# esp8266_ver3.net
KiCad netlist of a schematic drawn in EAGLE
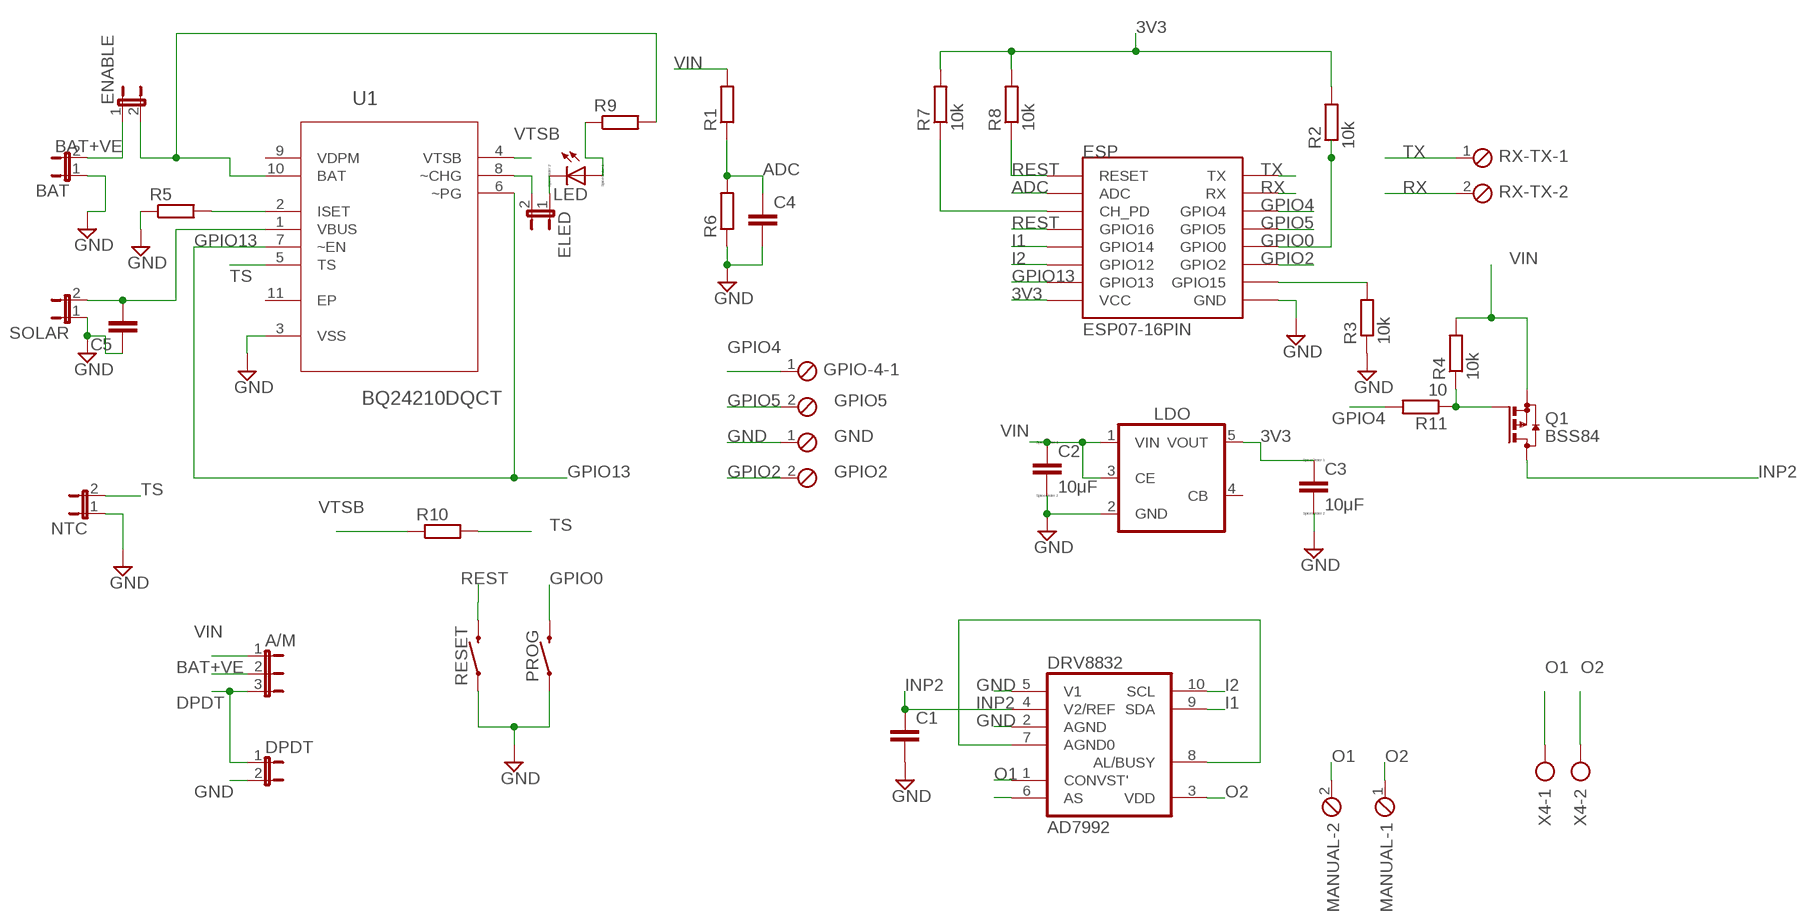
[diagram p0: schematic, sheet 1]

(export (version "E")
  (design (tool "Eeschema 10.0.6"))
  (components
    (comp (ref "A/M")
      (value "JP2E")
      (footprint "eagle-import:JP2")
      (libsource (lib "eagle-import") (part "JP2E"))
    )
    (comp (ref "BAT")
      (value "JP1E")
      (footprint "eagle-import:JP1")
      (libsource (lib "eagle-import") (part "JP1E"))
    )
    (comp (ref "C1")
      (value "C-EUC0805K")
      (footprint "eagle-import:C0805K")
      (libsource (lib "eagle-import") (part "C-EUC0805K"))
    )
    (comp (ref "C2")
      (value "10μF")
      (footprint "eagle-import:C1206")
      (libsource (lib "eagle-import") (part "CC1206"))
    )
    (comp (ref "C3")
      (value "10μF")
      (footprint "eagle-import:C1206")
      (libsource (lib "eagle-import") (part "CC1206"))
    )
    (comp (ref "C4")
      (value "C-EUC1206")
      (footprint "eagle-import:C1206")
      (libsource (lib "eagle-import") (part "C-EUC1206"))
    )
    (comp (ref "C5")
      (value "C-EUC1206")
      (footprint "eagle-import:C1206")
      (libsource (lib "eagle-import") (part "C-EUC1206"))
    )
    (comp (ref "DPDT")
      (value "JP1E")
      (footprint "eagle-import:JP1")
      (libsource (lib "eagle-import") (part "JP1E"))
    )
    (comp (ref "DRV8832")
      (value "AD7992")
      (footprint "eagle-import:MSOP10")
      (libsource (lib "eagle-import") (part "AD7992"))
    )
    (comp (ref "ELED")
      (value "JP1E")
      (footprint "eagle-import:JP1")
      (libsource (lib "eagle-import") (part "JP1E"))
    )
    (comp (ref "ENABLE")
      (value "JP1E")
      (footprint "eagle-import:JP1")
      (libsource (lib "eagle-import") (part "JP1E"))
    )
    (comp (ref "ESP")
      (value "ESP07-16PIN")
      (footprint "eagle-import:ESP07-16PIN")
      (libsource (lib "eagle-import") (part "ESP07-16PIN"))
    )
    (comp (ref "GPIO-4")
      (value "MPT2")
      (footprint "eagle-import:2POL254")
      (libsource (lib "eagle-import") (part "con-phoenix-254_172_MPT2"))
    )
    (comp (ref "LDO")
      (value "TS5205")
      (footprint "eagle-import:SOT25")
      (libsource (lib "eagle-import") (part "TS5205"))
    )
    (comp (ref "LED")
      (value "LED_E")
      (footprint "eagle-import:LED_1206")
      (libsource (lib "eagle-import") (part "LED_E"))
    )
    (comp (ref "MANUAL")
      (value "MPT2")
      (footprint "eagle-import:2POL254")
      (libsource (lib "eagle-import") (part "con-phoenix-254_172_MPT2"))
    )
    (comp (ref "NTC")
      (value "JP1E")
      (footprint "eagle-import:JP1")
      (libsource (lib "eagle-import") (part "JP1E"))
    )
    (comp (ref "PROG")
      (value "MOMENTARY-SWITCH-SPST-SMD-5.2MM")
      (footprint "eagle-import:TACTILE_SWITCH_SMD_5.2MM")
      (libsource (lib "eagle-import") (part "MOMENTARY-SWITCH-SPST-SMD-5.2MM"))
    )
    (comp (ref "Q1")
      (value "BSS84")
      (footprint "eagle-import:SOT23")
      (libsource (lib "eagle-import") (part "BSS84"))
    )
    (comp (ref "R1")
      (value "R-EU_R1206")
      (footprint "eagle-import:R1206")
      (libsource (lib "eagle-import") (part "resistor_348_R-EU_R1206"))
    )
    (comp (ref "R2")
      (value "10k")
      (footprint "eagle-import:R1206")
      (libsource (lib "eagle-import") (part "R-EU_R1206"))
    )
    (comp (ref "R3")
      (value "10k")
      (footprint "eagle-import:R1206")
      (libsource (lib "eagle-import") (part "R-EU_R1206"))
    )
    (comp (ref "R4")
      (value "10k")
      (footprint "eagle-import:R1206")
      (libsource (lib "eagle-import") (part "resistor_348_R-EU_R1206"))
    )
    (comp (ref "R5")
      (value "R-EU_R1206")
      (footprint "eagle-import:R1206")
      (libsource (lib "eagle-import") (part "resistor_348_R-EU_R1206"))
    )
    (comp (ref "R6")
      (value "R-EU_R1206")
      (footprint "eagle-import:R1206")
      (libsource (lib "eagle-import") (part "resistor_348_R-EU_R1206"))
    )
    (comp (ref "R7")
      (value "10k")
      (footprint "eagle-import:R1206")
      (libsource (lib "eagle-import") (part "R-EU_R1206"))
    )
    (comp (ref "R8")
      (value "10k")
      (footprint "eagle-import:R1206")
      (libsource (lib "eagle-import") (part "R-EU_R1206"))
    )
    (comp (ref "R9")
      (value "R-EU_R1206")
      (footprint "eagle-import:R1206")
      (libsource (lib "eagle-import") (part "resistor_348_R-EU_R1206"))
    )
    (comp (ref "R10")
      (value "R-EU_R1206")
      (footprint "eagle-import:R1206")
      (libsource (lib "eagle-import") (part "resistor_348_R-EU_R1206"))
    )
    (comp (ref "R11")
      (value "10")
      (footprint "eagle-import:R1206")
      (libsource (lib "eagle-import") (part "resistor_348_R-EU_R1206"))
    )
    (comp (ref "RESET")
      (value "MOMENTARY-SWITCH-SPST-SMD-5.2MM")
      (footprint "eagle-import:TACTILE_SWITCH_SMD_5.2MM")
      (libsource (lib "eagle-import") (part "MOMENTARY-SWITCH-SPST-SMD-5.2MM"))
    )
    (comp (ref "RX-TX")
      (value "MPT2")
      (footprint "eagle-import:2POL254")
      (libsource (lib "eagle-import") (part "MPT2"))
    )
    (comp (ref "SOLAR")
      (value "JP1E")
      (footprint "eagle-import:JP1")
      (libsource (lib "eagle-import") (part "JP1E"))
    )
    (comp (ref "U1")
      (value "BQ24210DQCT")
      (footprint "eagle-import:SON50P200X300X80-11N")
      (libsource (lib "eagle-import") (part "BQ24210DQCT"))
    )
    (comp (ref "X2")
      (value "MPT2")
      (footprint "eagle-import:2POL254")
      (libsource (lib "eagle-import") (part "con-phoenix-254_172_MPT2"))
    )
    (comp (ref "X4")
      (value "AK300/2")
      (footprint "eagle-import:AK300_2")
      (libsource (lib "eagle-import") (part "AK300/2"))
    )
  )
  (nets
    (net (code "1") (name "/3V3") (class "Default")
      (node (ref "C3") (pin "1") (pinfunction "1_1") (pintype "passive"))
      (node (ref "ESP") (pin "VCC") (pinfunction "VCC_VCC") (pintype "bidirectional"))
      (node (ref "LDO") (pin "5") (pinfunction "VOUT_5") (pintype "passive"))
      (node (ref "R2") (pin "2") (pinfunction "2_2") (pintype "passive"))
      (node (ref "R7") (pin "2") (pinfunction "2_2") (pintype "passive"))
      (node (ref "R8") (pin "2") (pinfunction "2_2") (pintype "passive"))
    )
    (net (code "2") (name "/ADC") (class "Default")
      (node (ref "C4") (pin "1") (pinfunction "1_1") (pintype "passive"))
      (node (ref "ESP") (pin "ADC") (pinfunction "ADC_ADC") (pintype "bidirectional"))
      (node (ref "R1") (pin "1") (pinfunction "1_1") (pintype "passive"))
      (node (ref "R6") (pin "2") (pinfunction "2_2") (pintype "passive"))
    )
    (net (code "3") (name "/BAT+VE") (class "Default")
      (node (ref "A/M") (pin "2") (pinfunction "2_2") (pintype "passive"))
      (node (ref "BAT") (pin "2") (pinfunction "2_2") (pintype "passive"))
      (node (ref "ENABLE") (pin "1") (pinfunction "1_1") (pintype "passive"))
    )
    (net (code "4") (name "/DPDT") (class "Default")
      (node (ref "A/M") (pin "3") (pinfunction "3_3") (pintype "passive"))
      (node (ref "DPDT") (pin "1") (pinfunction "1_1") (pintype "passive"))
    )
    (net (code "5") (name "/GPIO0") (class "Default")
      (node (ref "ESP") (pin "GPIO0") (pinfunction "GPIO0_GPIO0") (pintype "bidirectional"))
      (node (ref "PROG") (pin "3") (pinfunction "2_3") (pintype "passive"))
      (node (ref "R2") (pin "1") (pinfunction "1_1") (pintype "passive"))
    )
    (net (code "6") (name "/GPIO2") (class "Default")
      (node (ref "ESP") (pin "GPIO2") (pinfunction "GPIO2_GPIO2") (pintype "bidirectional"))
      (node (ref "X2") (pin "2") (pinfunction "1_2") (pintype "passive"))
    )
    (net (code "7") (name "/GPIO4") (class "Default")
      (node (ref "ESP") (pin "GPIO4") (pinfunction "GPIO4_GPIO4") (pintype "bidirectional"))
      (node (ref "GPIO-4") (pin "1") (pinfunction "1_1") (pintype "passive"))
      (node (ref "R11") (pin "2") (pinfunction "2_2") (pintype "passive"))
    )
    (net (code "8") (name "/GPIO5") (class "Default")
      (node (ref "ESP") (pin "GPIO5") (pinfunction "GPIO5_GPIO5") (pintype "bidirectional"))
      (node (ref "GPIO-4") (pin "2") (pinfunction "1_2") (pintype "passive"))
    )
    (net (code "9") (name "/GPIO13") (class "Default")
      (node (ref "ESP") (pin "GPIO13") (pinfunction "GPIO13_GPIO13") (pintype "bidirectional"))
      (node (ref "U1") (pin "6") (pinfunction "~{PG}_6") (pintype "output"))
      (node (ref "U1") (pin "7") (pinfunction "~{EN}_7") (pintype "input"))
    )
    (net (code "10") (name "/I1") (class "Default")
      (node (ref "DRV8832") (pin "9") (pinfunction "SDA_9") (pintype "output"))
      (node (ref "ESP") (pin "GPIO14") (pinfunction "GPIO14_GPIO14") (pintype "bidirectional"))
    )
    (net (code "11") (name "/I2") (class "Default")
      (node (ref "DRV8832") (pin "10") (pinfunction "SCL_10") (pintype "output"))
      (node (ref "ESP") (pin "GPIO12") (pinfunction "GPIO12_GPIO12") (pintype "bidirectional"))
    )
    (net (code "12") (name "/INP2") (class "Default")
      (node (ref "C1") (pin "1") (pinfunction "1_1") (pintype "passive"))
      (node (ref "DRV8832") (pin "4") (pinfunction "V2/REF_4") (pintype "input"))
      (node (ref "Q1") (pin "3") (pinfunction "D_3") (pintype "passive"))
    )
    (net (code "13") (name "/O1") (class "Default")
      (node (ref "DRV8832") (pin "1") (pinfunction "CONVST'_1") (pintype "input"))
      (node (ref "MANUAL") (pin "2") (pinfunction "1_2") (pintype "passive"))
      (node (ref "X4") (pin "1") (pinfunction "KL_1") (pintype "passive"))
    )
    (net (code "14") (name "/O2") (class "Default")
      (node (ref "DRV8832") (pin "3") (pinfunction "VDD_3") (pintype "power_in"))
      (node (ref "MANUAL") (pin "1") (pinfunction "1_1") (pintype "passive"))
      (node (ref "X4") (pin "2") (pinfunction "KL_2") (pintype "passive"))
    )
    (net (code "15") (name "/REST") (class "Default")
      (node (ref "ESP") (pin "GPIO16") (pinfunction "GPIO16_GPIO16") (pintype "bidirectional"))
      (node (ref "ESP") (pin "REST") (pinfunction "RESET_REST") (pintype "bidirectional"))
      (node (ref "R8") (pin "1") (pinfunction "1_1") (pintype "passive"))
      (node (ref "RESET") (pin "3") (pinfunction "2_3") (pintype "passive"))
    )
    (net (code "16") (name "/RX") (class "Default")
      (node (ref "ESP") (pin "RX") (pinfunction "RX_RX") (pintype "bidirectional"))
      (node (ref "RX-TX") (pin "2") (pinfunction "1_2") (pintype "passive"))
    )
    (net (code "17") (name "/TS") (class "Default")
      (node (ref "NTC") (pin "2") (pinfunction "2_2") (pintype "passive"))
      (node (ref "R10") (pin "2") (pinfunction "2_2") (pintype "passive"))
      (node (ref "U1") (pin "5") (pinfunction "TS_5") (pintype "input"))
    )
    (net (code "18") (name "/TX") (class "Default")
      (node (ref "ESP") (pin "TX") (pinfunction "TX_TX") (pintype "bidirectional"))
      (node (ref "RX-TX") (pin "1") (pinfunction "1_1") (pintype "passive"))
    )
    (net (code "19") (name "/VIN") (class "Default")
      (node (ref "A/M") (pin "1") (pinfunction "1_1") (pintype "passive"))
      (node (ref "C2") (pin "1") (pinfunction "1_1") (pintype "passive"))
      (node (ref "LDO") (pin "1") (pinfunction "VIN_1") (pintype "input"))
      (node (ref "LDO") (pin "3") (pinfunction "CE_3") (pintype "input"))
      (node (ref "Q1") (pin "2") (pinfunction "S_2") (pintype "passive"))
      (node (ref "R1") (pin "2") (pinfunction "2_2") (pintype "passive"))
      (node (ref "R4") (pin "2") (pinfunction "2_2") (pintype "passive"))
    )
    (net (code "20") (name "/VTSB") (class "Default")
      (node (ref "R10") (pin "1") (pinfunction "1_1") (pintype "passive"))
      (node (ref "U1") (pin "4") (pinfunction "VTSB_4") (pintype "output"))
    )
    (net (code "21") (name "GND") (class "Default")
      (node (ref "BAT") (pin "1") (pinfunction "1_1") (pintype "passive"))
      (node (ref "C1") (pin "2") (pinfunction "2_2") (pintype "passive"))
      (node (ref "C2") (pin "2") (pinfunction "2_2") (pintype "passive"))
      (node (ref "C3") (pin "2") (pinfunction "2_2") (pintype "passive"))
      (node (ref "C4") (pin "2") (pinfunction "2_2") (pintype "passive"))
      (node (ref "C5") (pin "1") (pinfunction "1_1") (pintype "passive"))
      (node (ref "DPDT") (pin "2") (pinfunction "2_2") (pintype "passive"))
      (node (ref "DRV8832") (pin "2") (pinfunction "AGND_2") (pintype "power_in"))
      (node (ref "DRV8832") (pin "5") (pinfunction "V1_5") (pintype "input"))
      (node (ref "ESP") (pin "GND") (pinfunction "GND_GND") (pintype "bidirectional"))
      (node (ref "LDO") (pin "2") (pinfunction "GND_2") (pintype "passive"))
      (node (ref "NTC") (pin "1") (pinfunction "1_1") (pintype "passive"))
      (node (ref "PROG") (pin "1") (pinfunction "1_1") (pintype "passive"))
      (node (ref "R3") (pin "1") (pinfunction "1_1") (pintype "passive"))
      (node (ref "R5") (pin "1") (pinfunction "1_1") (pintype "passive"))
      (node (ref "R6") (pin "1") (pinfunction "1_1") (pintype "passive"))
      (node (ref "RESET") (pin "1") (pinfunction "1_1") (pintype "passive"))
      (node (ref "SOLAR") (pin "1") (pinfunction "1_1") (pintype "passive"))
      (node (ref "U1") (pin "3") (pinfunction "VSS_3") (pintype "passive"))
      (node (ref "X2") (pin "1") (pinfunction "1_1") (pintype "passive"))
    )
    (net (code "22") (name "Net-(DRV8832-AGND0)") (class "Default")
      (node (ref "DRV8832") (pin "7") (pinfunction "AGND0_7") (pintype "power_in"))
      (node (ref "DRV8832") (pin "8") (pinfunction "AL/BUSY_8") (pintype "output"))
    )
    (net (code "23") (name "Net-(ELED-Pad1)") (class "Default")
      (node (ref "ELED") (pin "1") (pinfunction "1_1") (pintype "passive"))
      (node (ref "LED") (pin "C") (pinfunction "C_C") (pintype "passive"))
    )
    (net (code "24") (name "Net-(ESP-PadCH_PD)") (class "Default")
      (node (ref "ESP") (pin "CH_PD") (pinfunction "CH_PD_CH_PD") (pintype "bidirectional"))
      (node (ref "R7") (pin "1") (pinfunction "1_1") (pintype "passive"))
    )
    (net (code "25") (name "Net-(ESP-PadGPIO15)") (class "Default")
      (node (ref "ESP") (pin "GPIO15") (pinfunction "GPIO15_GPIO15") (pintype "bidirectional"))
      (node (ref "R3") (pin "2") (pinfunction "2_2") (pintype "passive"))
    )
    (net (code "26") (name "Net-(LED-PadA)") (class "Default")
      (node (ref "LED") (pin "A") (pinfunction "A_A") (pintype "passive"))
      (node (ref "R9") (pin "1") (pinfunction "1_1") (pintype "passive"))
    )
    (net (code "27") (name "Net-(Q1-G)") (class "Default")
      (node (ref "Q1") (pin "1") (pinfunction "G_1") (pintype "passive"))
      (node (ref "R11") (pin "1") (pinfunction "1_1") (pintype "passive"))
      (node (ref "R4") (pin "1") (pinfunction "1_1") (pintype "passive"))
    )
    (net (code "28") (name "Net-(U1-BAT)") (class "Default")
      (node (ref "ENABLE") (pin "2") (pinfunction "2_2") (pintype "passive"))
      (node (ref "R9") (pin "2") (pinfunction "2_2") (pintype "passive"))
      (node (ref "U1") (pin "10") (pinfunction "BAT_10") (pintype "bidirectional"))
    )
    (net (code "29") (name "Net-(U1-ISET)") (class "Default")
      (node (ref "R5") (pin "2") (pinfunction "2_2") (pintype "passive"))
      (node (ref "U1") (pin "2") (pinfunction "ISET_2") (pintype "input"))
    )
    (net (code "30") (name "Net-(U1-VBUS)") (class "Default")
      (node (ref "C5") (pin "2") (pinfunction "2_2") (pintype "passive"))
      (node (ref "SOLAR") (pin "2") (pinfunction "2_2") (pintype "passive"))
      (node (ref "U1") (pin "1") (pinfunction "VBUS_1") (pintype "bidirectional"))
    )
    (net (code "31") (name "Net-(U1-~{CHG})") (class "Default")
      (node (ref "ELED") (pin "2") (pinfunction "2_2") (pintype "passive"))
      (node (ref "U1") (pin "8") (pinfunction "~{CHG}_8") (pintype "output"))
    )
    (net (code "32") (name "unconnected-(DRV8832-AS-Pad6)") (class "Default")
      (node (ref "DRV8832") (pin "6") (pinfunction "AS_6") (pintype "input"))
    )
    (net (code "33") (name "unconnected-(LDO-CB-Pad4)") (class "Default")
      (node (ref "LDO") (pin "4") (pinfunction "CB_4") (pintype "input"))
    )
    (net (code "34") (name "unconnected-(U1-EP-Pad11)") (class "Default")
      (node (ref "U1") (pin "11") (pinfunction "EP_11") (pintype "passive"))
    )
    (net (code "35") (name "unconnected-(U1-VDPM-Pad9)") (class "Default")
      (node (ref "U1") (pin "9") (pinfunction "VDPM_9") (pintype "input"))
    )
  )
)
